# deska_uprava.net
KiCad netlist of a schematic drawn in EAGLE
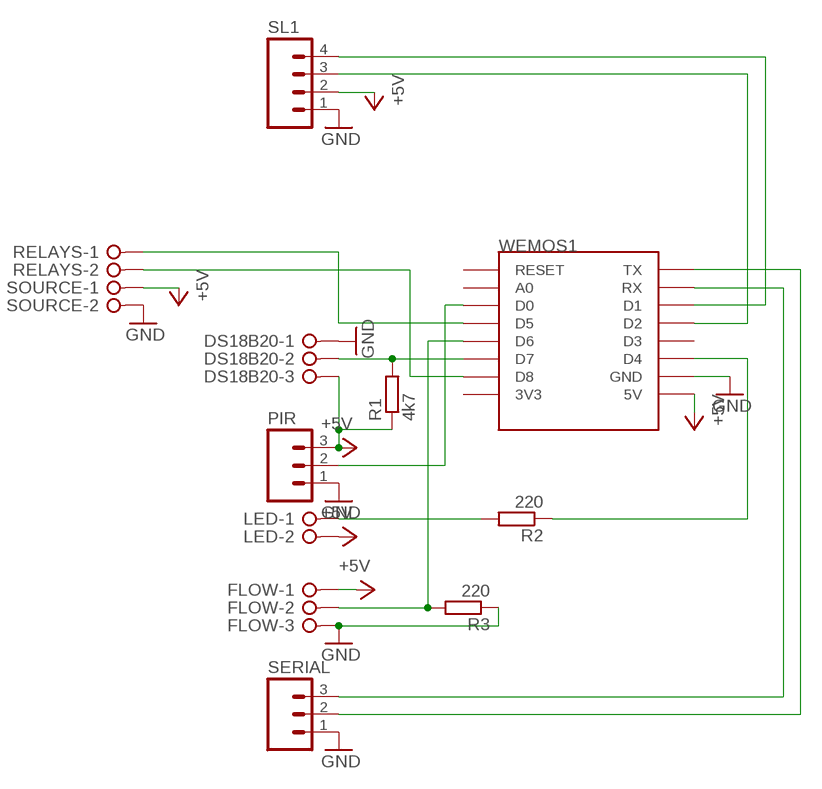
[diagram p0: schematic, sheet 1]

(export (version "E")
  (design (tool "Eeschema 10.0.6"))
  (components
    (comp (ref "DS18B20")
      (value "W237-03P")
      (footprint "eagle-import:W237-133")
      (libsource (lib "eagle-import") (part "W237-03P"))
    )
    (comp (ref "FLOW")
      (value "W237-03P")
      (footprint "eagle-import:W237-133")
      (libsource (lib "eagle-import") (part "W237-03P"))
    )
    (comp (ref "LED")
      (value "W237-02P")
      (footprint "eagle-import:W237-132")
      (libsource (lib "eagle-import") (part "W237-02P"))
    )
    (comp (ref "PIR")
      (value "M03")
      (footprint "eagle-import:03P")
      (libsource (lib "eagle-import") (part "M03"))
    )
    (comp (ref "R1")
      (value "4k7")
      (footprint "eagle-import:0207_10")
      (libsource (lib "eagle-import") (part "R-EU_0207/10"))
    )
    (comp (ref "R2")
      (value "220")
      (footprint "eagle-import:0207_10")
      (libsource (lib "eagle-import") (part "R-EU_0207/10"))
    )
    (comp (ref "R3")
      (value "220")
      (footprint "eagle-import:0207_10")
      (libsource (lib "eagle-import") (part "R-EU_0207/10"))
    )
    (comp (ref "RELAYS")
      (value "W237-02P")
      (footprint "eagle-import:W237-132")
      (libsource (lib "eagle-import") (part "W237-02P"))
    )
    (comp (ref "SERIAL")
      (value "M03")
      (footprint "eagle-import:03P")
      (libsource (lib "eagle-import") (part "M03"))
    )
    (comp (ref "SL1")
      (value "M04")
      (footprint "eagle-import:04P")
      (libsource (lib "eagle-import") (part "M04"))
    )
    (comp (ref "SOURCE")
      (value "W237-02P")
      (footprint "eagle-import:W237-132")
      (libsource (lib "eagle-import") (part "W237-02P"))
    )
    (comp (ref "WEMOS1")
      (value "WEMOS-D1-MINI")
      (footprint "eagle-import:WEMOS-D1-MINI")
      (libsource (lib "eagle-import") (part "WEMOS-D1-MINI"))
    )
  )
  (nets
    (net (code "1") (name "+5V") (class "Default")
      (node (ref "DS18B20") (pin "3") (pinfunction "KL_3") (pintype "passive"))
      (node (ref "FLOW") (pin "1") (pinfunction "KL_1") (pintype "passive"))
      (node (ref "LED") (pin "2") (pinfunction "KL_2") (pintype "passive"))
      (node (ref "PIR") (pin "3") (pinfunction "3_3") (pintype "passive"))
      (node (ref "R1") (pin "1") (pinfunction "1_1") (pintype "passive"))
      (node (ref "SL1") (pin "2") (pinfunction "2_2") (pintype "passive"))
      (node (ref "SOURCE") (pin "1") (pinfunction "KL_1") (pintype "passive"))
      (node (ref "WEMOS1") (pin "5V") (pinfunction "5V_5V") (pintype "bidirectional"))
    )
    (net (code "2") (name "GND") (class "Default")
      (node (ref "DS18B20") (pin "1") (pinfunction "KL_1") (pintype "passive"))
      (node (ref "FLOW") (pin "3") (pinfunction "KL_3") (pintype "passive"))
      (node (ref "PIR") (pin "1") (pinfunction "1_1") (pintype "passive"))
      (node (ref "R3") (pin "1") (pinfunction "1_1") (pintype "passive"))
      (node (ref "SERIAL") (pin "1") (pinfunction "1_1") (pintype "passive"))
      (node (ref "SL1") (pin "1") (pinfunction "1_1") (pintype "passive"))
      (node (ref "SOURCE") (pin "2") (pinfunction "KL_2") (pintype "passive"))
      (node (ref "WEMOS1") (pin "GND") (pinfunction "GND_GND") (pintype "bidirectional"))
    )
    (net (code "3") (name "Net-(DS18B20B-KL)") (class "Default")
      (node (ref "DS18B20") (pin "2") (pinfunction "KL_2") (pintype "passive"))
      (node (ref "R1") (pin "2") (pinfunction "2_2") (pintype "passive"))
      (node (ref "WEMOS1") (pin "D7") (pinfunction "D7_D7") (pintype "bidirectional"))
    )
    (net (code "4") (name "Net-(FLOWB-KL)") (class "Default")
      (node (ref "FLOW") (pin "2") (pinfunction "KL_2") (pintype "passive"))
      (node (ref "R3") (pin "2") (pinfunction "2_2") (pintype "passive"))
      (node (ref "WEMOS1") (pin "D6") (pinfunction "D6_D6") (pintype "bidirectional"))
    )
    (net (code "5") (name "Net-(LEDA-KL)") (class "Default")
      (node (ref "LED") (pin "1") (pinfunction "KL_1") (pintype "passive"))
      (node (ref "R2") (pin "2") (pinfunction "2_2") (pintype "passive"))
    )
    (net (code "6") (name "Net-(PIR-Pad2)") (class "Default")
      (node (ref "PIR") (pin "2") (pinfunction "2_2") (pintype "passive"))
      (node (ref "WEMOS1") (pin "D0") (pinfunction "D0_D0") (pintype "bidirectional"))
    )
    (net (code "7") (name "Net-(R2-Pad1)") (class "Default")
      (node (ref "R2") (pin "1") (pinfunction "1_1") (pintype "passive"))
      (node (ref "WEMOS1") (pin "D4") (pinfunction "D4_D4") (pintype "bidirectional"))
    )
    (net (code "8") (name "Net-(RELAYSA-KL)") (class "Default")
      (node (ref "RELAYS") (pin "1") (pinfunction "KL_1") (pintype "passive"))
      (node (ref "WEMOS1") (pin "D5") (pinfunction "D5_D5") (pintype "bidirectional"))
    )
    (net (code "9") (name "Net-(RELAYSB-KL)") (class "Default")
      (node (ref "RELAYS") (pin "2") (pinfunction "KL_2") (pintype "passive"))
      (node (ref "WEMOS1") (pin "D8") (pinfunction "D8_D8") (pintype "bidirectional"))
    )
    (net (code "10") (name "Net-(SERIAL-Pad2)") (class "Default")
      (node (ref "SERIAL") (pin "2") (pinfunction "2_2") (pintype "passive"))
      (node (ref "WEMOS1") (pin "TX") (pinfunction "TX_TX") (pintype "bidirectional"))
    )
    (net (code "11") (name "Net-(SERIAL-Pad3)") (class "Default")
      (node (ref "SERIAL") (pin "3") (pinfunction "3_3") (pintype "passive"))
      (node (ref "WEMOS1") (pin "RX") (pinfunction "RX_RX") (pintype "bidirectional"))
    )
    (net (code "12") (name "Net-(SL1-Pad3)") (class "Default")
      (node (ref "SL1") (pin "3") (pinfunction "3_3") (pintype "passive"))
      (node (ref "WEMOS1") (pin "D2") (pinfunction "D2_D2") (pintype "bidirectional"))
    )
    (net (code "13") (name "Net-(SL1-Pad4)") (class "Default")
      (node (ref "SL1") (pin "4") (pinfunction "4_4") (pintype "passive"))
      (node (ref "WEMOS1") (pin "D1") (pinfunction "D1_D1") (pintype "bidirectional"))
    )
    (net (code "14") (name "unconnected-(WEMOS1-Pad3V3)") (class "Default")
      (node (ref "WEMOS1") (pin "3V3") (pinfunction "3V3_3V3") (pintype "bidirectional"))
    )
    (net (code "15") (name "unconnected-(WEMOS1-PadA0)") (class "Default")
      (node (ref "WEMOS1") (pin "A0") (pinfunction "A0_A0") (pintype "bidirectional"))
    )
    (net (code "16") (name "unconnected-(WEMOS1-PadD3)") (class "Default")
      (node (ref "WEMOS1") (pin "D3") (pinfunction "D3_D3") (pintype "bidirectional"))
    )
    (net (code "17") (name "unconnected-(WEMOS1-PadRESET)") (class "Default")
      (node (ref "WEMOS1") (pin "RESET") (pinfunction "RESET_RESET") (pintype "bidirectional"))
    )
  )
)
